# rgbsh.net
KiCad netlist of a schematic drawn in EAGLE
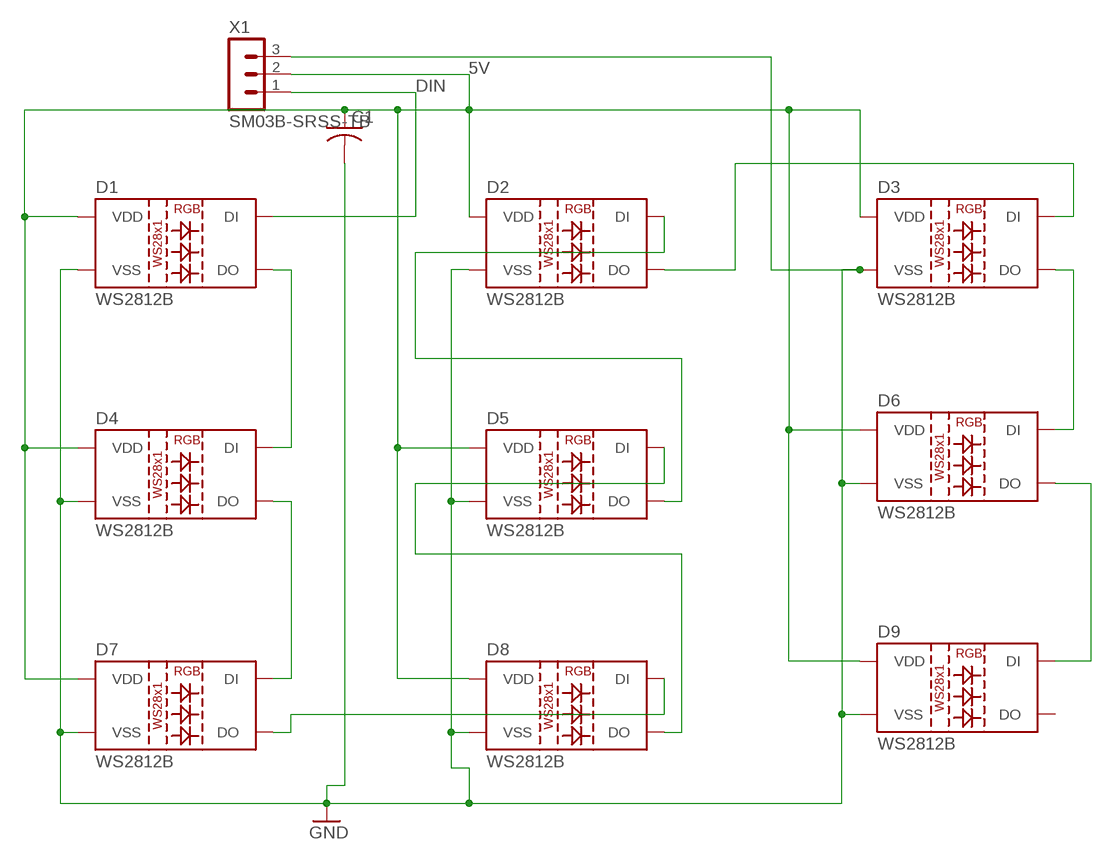
[diagram p0: schematic, sheet 1]

(export (version "E")
  (design (tool "Eeschema 10.0.6"))
  (components
    (comp (ref "C1")
      (value "C-USC0805K")
      (footprint "eagle-import:C0805K")
      (libsource (lib "eagle-import") (part "C-USC0805K"))
    )
    (comp (ref "D1")
      (value "WS2812B")
      (footprint "eagle-import:WS2812B")
      (libsource (lib "eagle-import") (part "WS2812B"))
    )
    (comp (ref "D2")
      (value "WS2812B")
      (footprint "eagle-import:WS2812B")
      (libsource (lib "eagle-import") (part "WS2812B"))
    )
    (comp (ref "D3")
      (value "WS2812B")
      (footprint "eagle-import:WS2812B")
      (libsource (lib "eagle-import") (part "WS2812B"))
    )
    (comp (ref "D4")
      (value "WS2812B")
      (footprint "eagle-import:WS2812B")
      (libsource (lib "eagle-import") (part "WS2812B"))
    )
    (comp (ref "D5")
      (value "WS2812B")
      (footprint "eagle-import:WS2812B")
      (libsource (lib "eagle-import") (part "WS2812B"))
    )
    (comp (ref "D6")
      (value "WS2812B")
      (footprint "eagle-import:WS2812B")
      (libsource (lib "eagle-import") (part "WS2812B"))
    )
    (comp (ref "D7")
      (value "WS2812B")
      (footprint "eagle-import:WS2812B")
      (libsource (lib "eagle-import") (part "WS2812B"))
    )
    (comp (ref "D8")
      (value "WS2812B")
      (footprint "eagle-import:WS2812B")
      (libsource (lib "eagle-import") (part "WS2812B"))
    )
    (comp (ref "D9")
      (value "WS2812B")
      (footprint "eagle-import:WS2812B")
      (libsource (lib "eagle-import") (part "WS2812B"))
    )
    (comp (ref "X1")
      (value "SM03B-SRSS-TB")
      (footprint "eagle-import:SM03B-SRSS-TB")
      (libsource (lib "eagle-import") (part "SM03B-SRSS-TB"))
    )
  )
  (nets
    (net (code "1") (name "/5V") (class "Default")
      (node (ref "C1") (pin "1") (pinfunction "1_1") (pintype "passive"))
      (node (ref "D1") (pin "1") (pinfunction "VDD_1") (pintype "bidirectional"))
      (node (ref "D2") (pin "1") (pinfunction "VDD_1") (pintype "bidirectional"))
      (node (ref "D3") (pin "1") (pinfunction "VDD_1") (pintype "bidirectional"))
      (node (ref "D4") (pin "1") (pinfunction "VDD_1") (pintype "bidirectional"))
      (node (ref "D5") (pin "1") (pinfunction "VDD_1") (pintype "bidirectional"))
      (node (ref "D6") (pin "1") (pinfunction "VDD_1") (pintype "bidirectional"))
      (node (ref "D7") (pin "1") (pinfunction "VDD_1") (pintype "bidirectional"))
      (node (ref "D8") (pin "1") (pinfunction "VDD_1") (pintype "bidirectional"))
      (node (ref "D9") (pin "1") (pinfunction "VDD_1") (pintype "bidirectional"))
      (node (ref "X1") (pin "2") (pinfunction "2_2") (pintype "passive"))
    )
    (net (code "2") (name "/DIN") (class "Default")
      (node (ref "D1") (pin "4") (pinfunction "DI_4") (pintype "bidirectional"))
      (node (ref "X1") (pin "1") (pinfunction "1_1") (pintype "passive"))
    )
    (net (code "3") (name "GND") (class "Default")
      (node (ref "C1") (pin "2") (pinfunction "2_2") (pintype "passive"))
      (node (ref "D1") (pin "3") (pinfunction "VSS_3") (pintype "bidirectional"))
      (node (ref "D2") (pin "3") (pinfunction "VSS_3") (pintype "bidirectional"))
      (node (ref "D3") (pin "3") (pinfunction "VSS_3") (pintype "bidirectional"))
      (node (ref "D4") (pin "3") (pinfunction "VSS_3") (pintype "bidirectional"))
      (node (ref "D5") (pin "3") (pinfunction "VSS_3") (pintype "bidirectional"))
      (node (ref "D6") (pin "3") (pinfunction "VSS_3") (pintype "bidirectional"))
      (node (ref "D7") (pin "3") (pinfunction "VSS_3") (pintype "bidirectional"))
      (node (ref "D8") (pin "3") (pinfunction "VSS_3") (pintype "bidirectional"))
      (node (ref "D9") (pin "3") (pinfunction "VSS_3") (pintype "bidirectional"))
      (node (ref "X1") (pin "3") (pinfunction "3_3") (pintype "passive"))
    )
    (net (code "4") (name "Net-(D1-DO)") (class "Default")
      (node (ref "D1") (pin "2") (pinfunction "DO_2") (pintype "bidirectional"))
      (node (ref "D4") (pin "4") (pinfunction "DI_4") (pintype "bidirectional"))
    )
    (net (code "5") (name "Net-(D2-DI)") (class "Default")
      (node (ref "D2") (pin "4") (pinfunction "DI_4") (pintype "bidirectional"))
      (node (ref "D5") (pin "2") (pinfunction "DO_2") (pintype "bidirectional"))
    )
    (net (code "6") (name "Net-(D2-DO)") (class "Default")
      (node (ref "D2") (pin "2") (pinfunction "DO_2") (pintype "bidirectional"))
      (node (ref "D3") (pin "4") (pinfunction "DI_4") (pintype "bidirectional"))
    )
    (net (code "7") (name "Net-(D3-DO)") (class "Default")
      (node (ref "D3") (pin "2") (pinfunction "DO_2") (pintype "bidirectional"))
      (node (ref "D6") (pin "4") (pinfunction "DI_4") (pintype "bidirectional"))
    )
    (net (code "8") (name "Net-(D4-DO)") (class "Default")
      (node (ref "D4") (pin "2") (pinfunction "DO_2") (pintype "bidirectional"))
      (node (ref "D7") (pin "4") (pinfunction "DI_4") (pintype "bidirectional"))
    )
    (net (code "9") (name "Net-(D5-DI)") (class "Default")
      (node (ref "D5") (pin "4") (pinfunction "DI_4") (pintype "bidirectional"))
      (node (ref "D8") (pin "2") (pinfunction "DO_2") (pintype "bidirectional"))
    )
    (net (code "10") (name "Net-(D6-DO)") (class "Default")
      (node (ref "D6") (pin "2") (pinfunction "DO_2") (pintype "bidirectional"))
      (node (ref "D9") (pin "4") (pinfunction "DI_4") (pintype "bidirectional"))
    )
    (net (code "11") (name "Net-(D7-DO)") (class "Default")
      (node (ref "D7") (pin "2") (pinfunction "DO_2") (pintype "bidirectional"))
      (node (ref "D8") (pin "4") (pinfunction "DI_4") (pintype "bidirectional"))
    )
    (net (code "12") (name "unconnected-(D9-DO-Pad2)") (class "Default")
      (node (ref "D9") (pin "2") (pinfunction "DO_2") (pintype "bidirectional"))
    )
  )
)
